# axiom_beta_interface_dummy_v0_9_c4a82e42.net
KiCad netlist of a schematic drawn in EAGLE
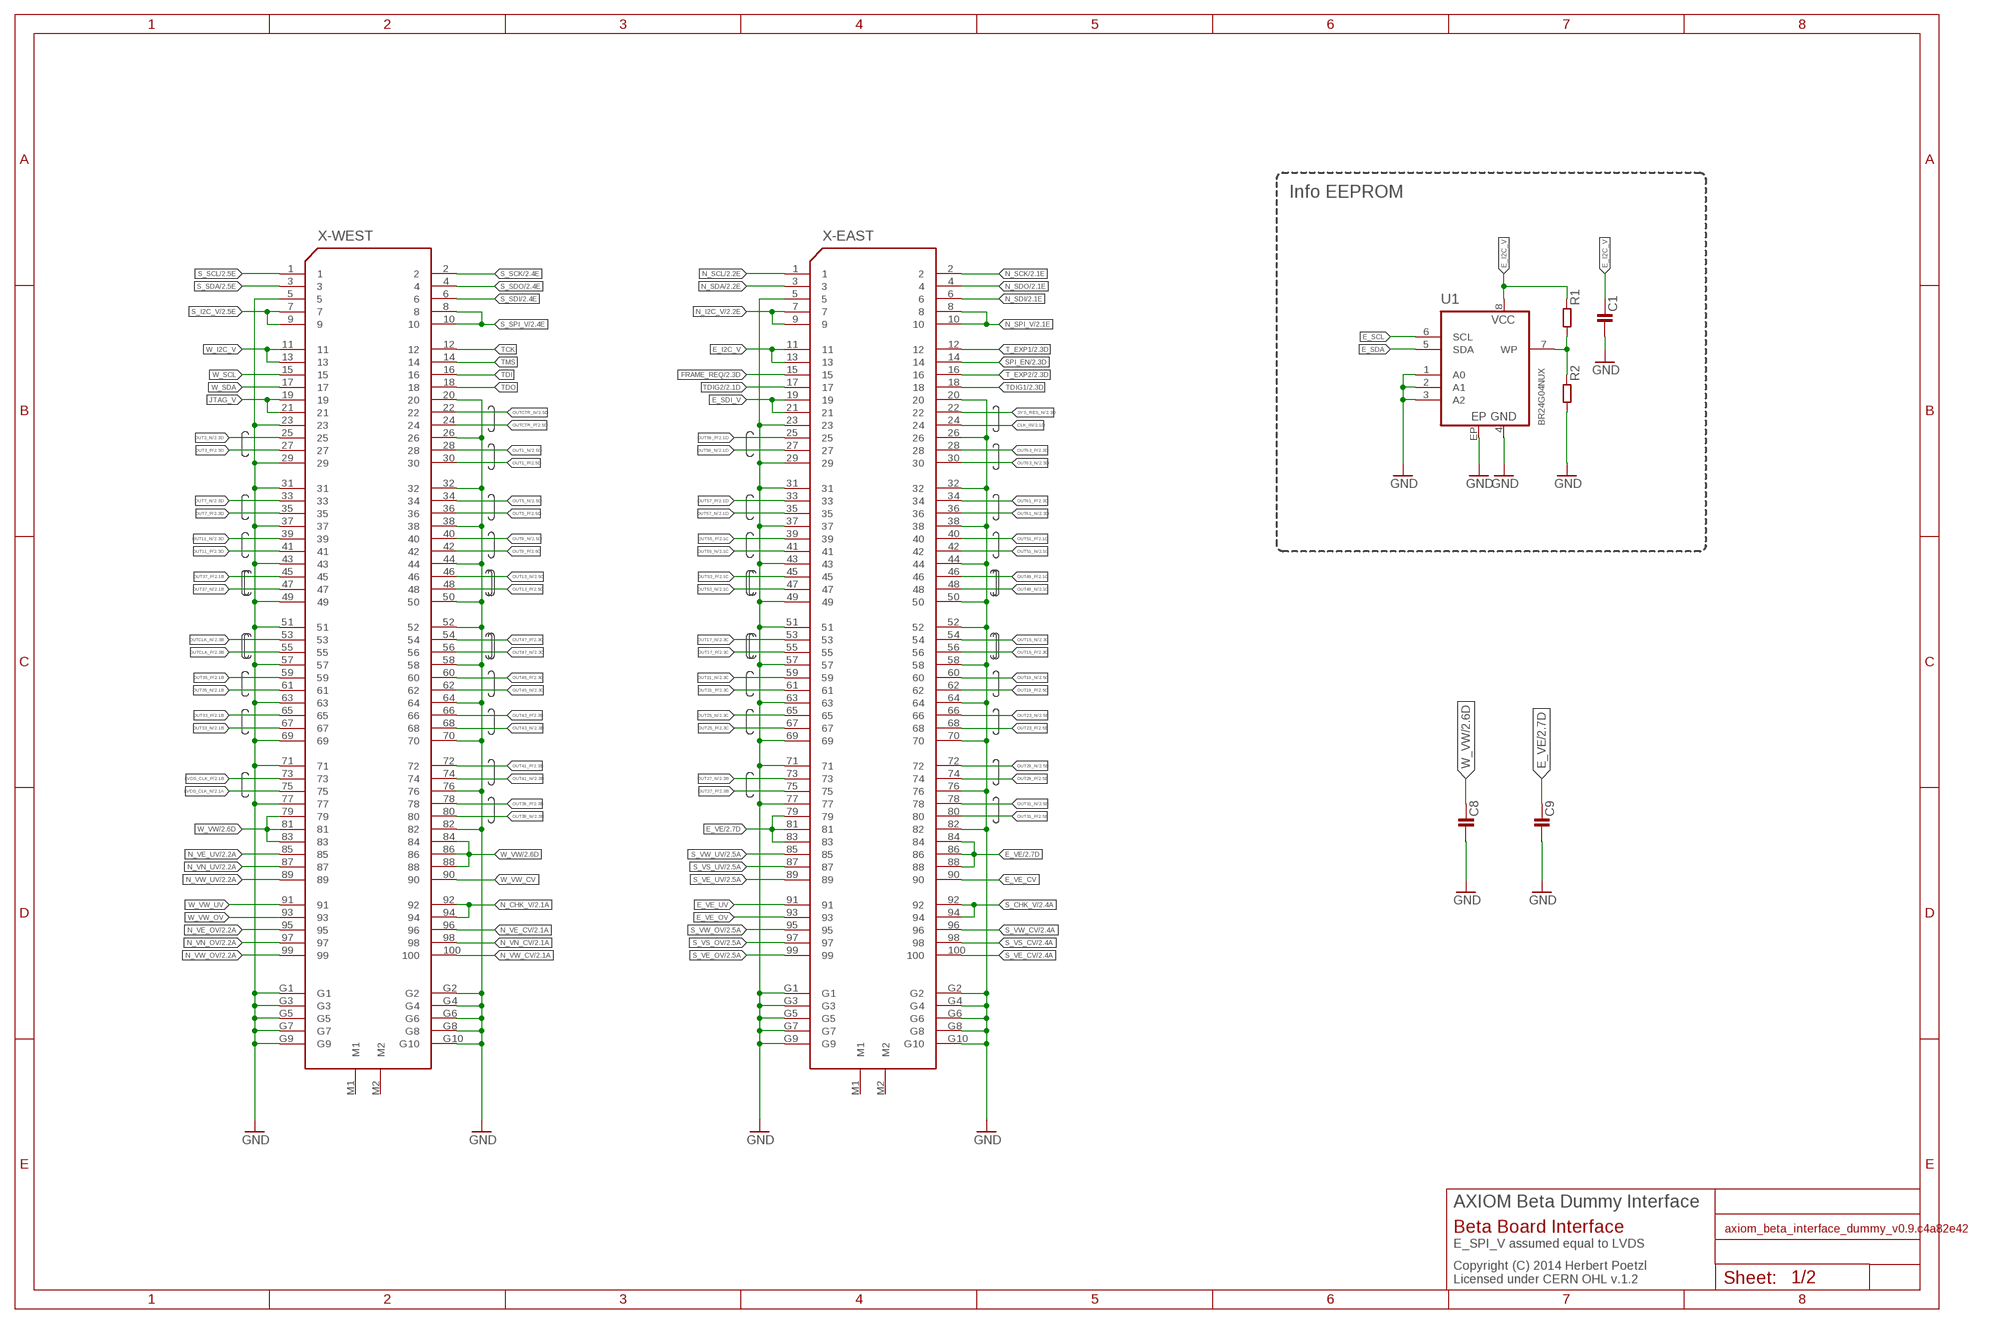
[diagram p0: schematic, sheet 1]
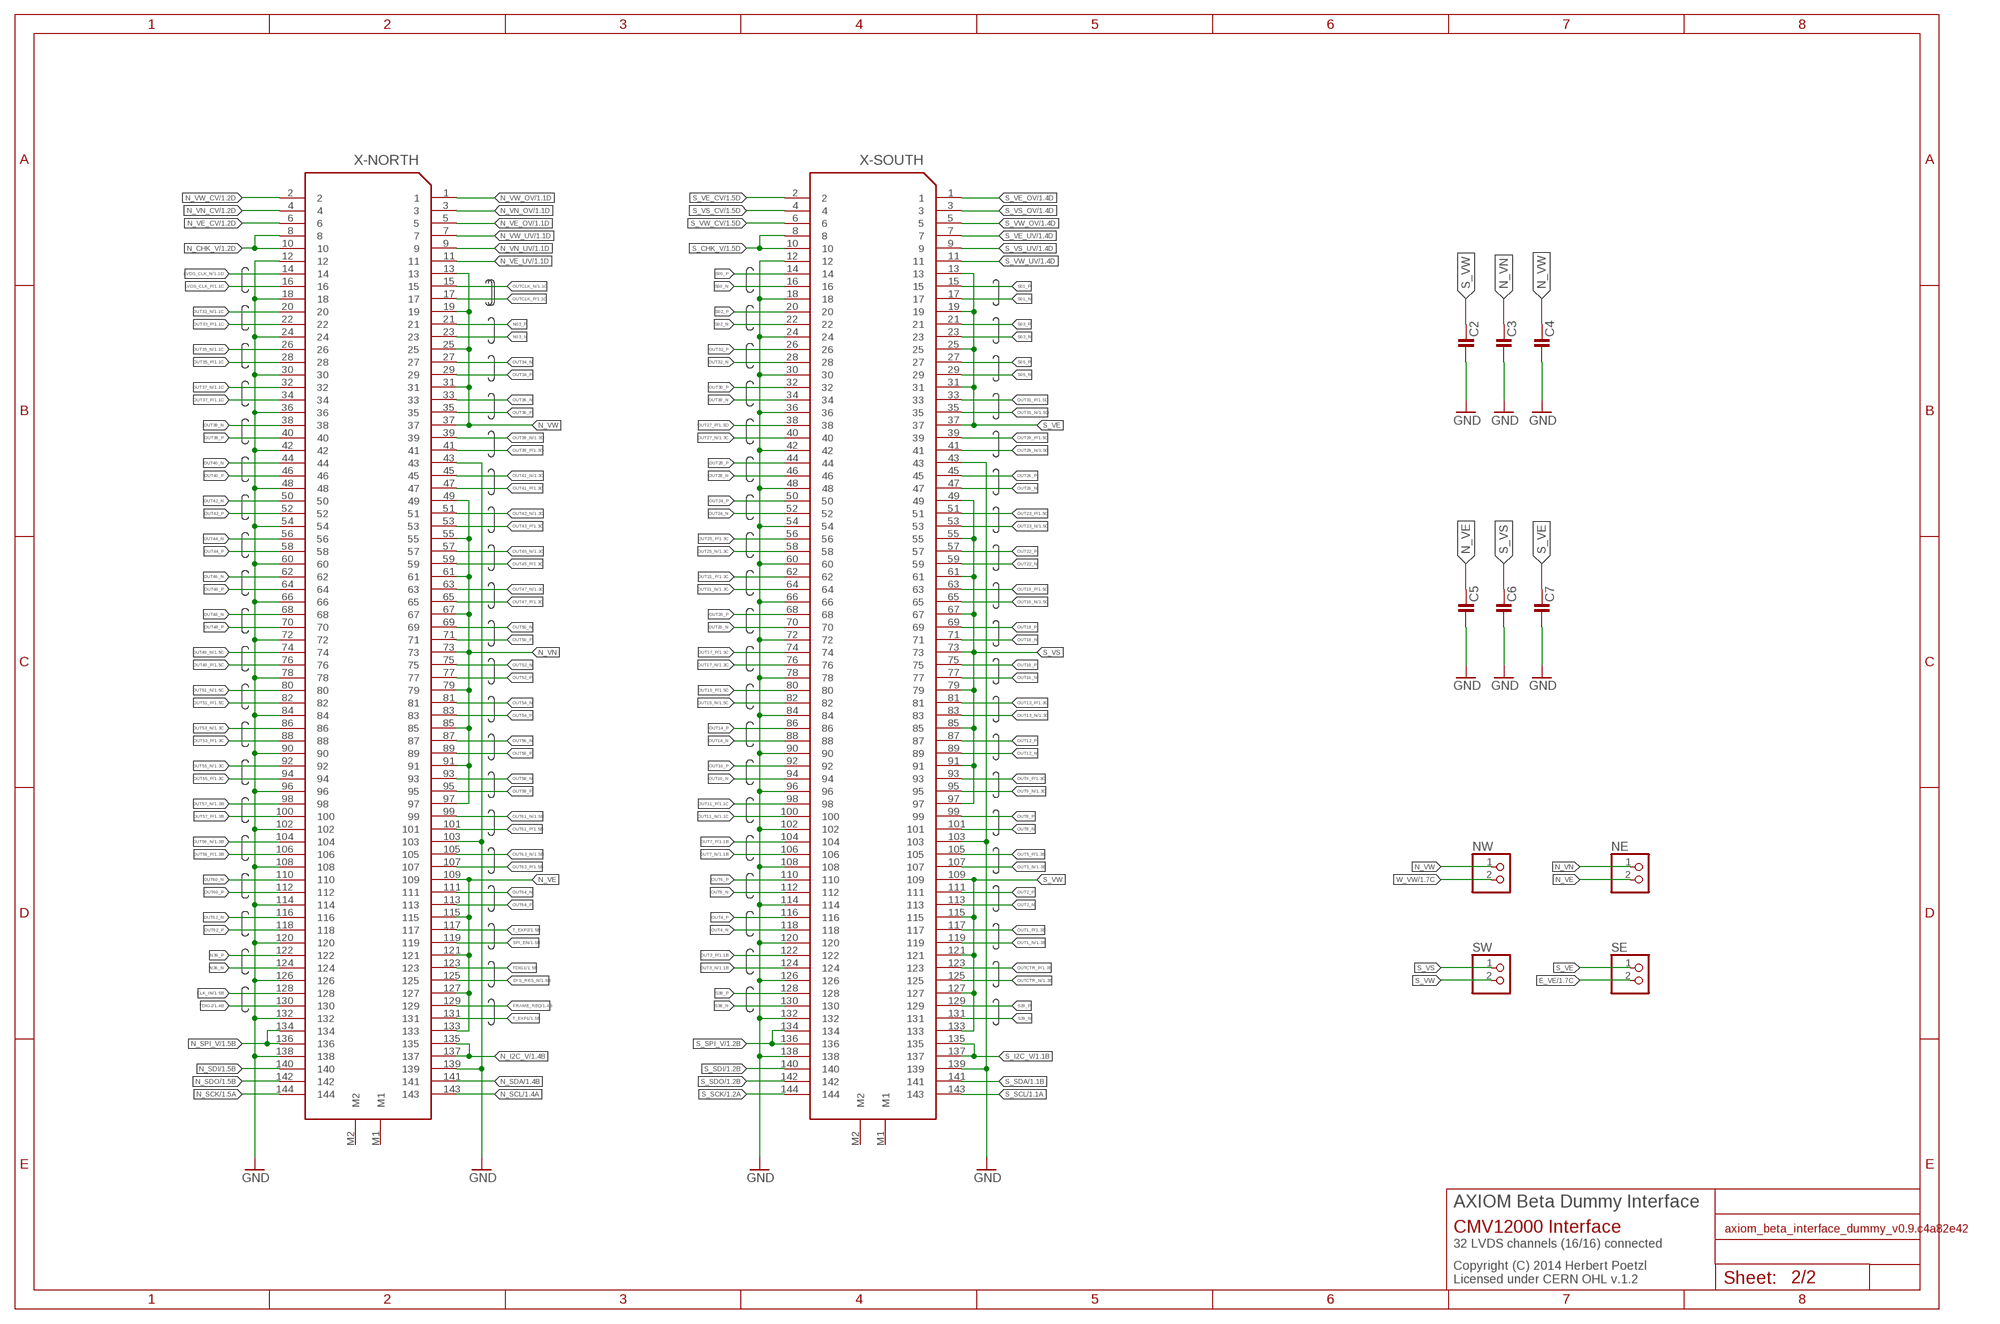
[diagram p1: schematic, sheet 2]

(export (version "E")
  (design (tool "Eeschema 10.0.6"))
  (components
    (comp (ref "C1")
      (value "C0402-B")
      (footprint "eagle-import:0402-B")
      (libsource (lib "eagle-import") (part "C0402-B"))
    )
    (comp (ref "C8")
      (value "C0805-B")
      (footprint "eagle-import:0805-B")
      (libsource (lib "eagle-import") (part "C0805-B"))
    )
    (comp (ref "C9")
      (value "C0805-B")
      (footprint "eagle-import:0805-B")
      (libsource (lib "eagle-import") (part "C0805-B"))
    )
    (comp (ref "R1")
      (value "R0402-B")
      (footprint "eagle-import:0402-B")
      (libsource (lib "eagle-import") (part "R0402-B"))
    )
    (comp (ref "R2")
      (value "R0402-B")
      (footprint "eagle-import:0402-B")
      (libsource (lib "eagle-import") (part "R0402-B"))
    )
    (comp (ref "U1")
      (value "BR24G04NUX")
      (footprint "eagle-import:DFN200X300X100-9N")
      (libsource (lib "eagle-import") (part "BR24G04NUX"))
    )
    (comp (ref "X-EAST")
      (value "FX10-100/10P")
      (footprint "eagle-import:FX10A-100P_10")
      (libsource (lib "eagle-import") (part "FX10-100/10P"))
    )
    (comp (ref "X-WEST")
      (value "FX10-100/10P")
      (footprint "eagle-import:FX10A-100P_10")
      (libsource (lib "eagle-import") (part "FX10-100/10P"))
    )
    (comp (ref "C2")
      (value "C0805-B")
      (footprint "eagle-import:0805-B")
      (libsource (lib "eagle-import") (part "C0805-B"))
    )
    (comp (ref "C3")
      (value "C0805-B")
      (footprint "eagle-import:0805-B")
      (libsource (lib "eagle-import") (part "C0805-B"))
    )
    (comp (ref "C4")
      (value "C0805-B")
      (footprint "eagle-import:0805-B")
      (libsource (lib "eagle-import") (part "C0805-B"))
    )
    (comp (ref "C5")
      (value "C0805-B")
      (footprint "eagle-import:0805-B")
      (libsource (lib "eagle-import") (part "C0805-B"))
    )
    (comp (ref "C6")
      (value "C0805-B")
      (footprint "eagle-import:0805-B")
      (libsource (lib "eagle-import") (part "C0805-B"))
    )
    (comp (ref "C7")
      (value "C0805-B")
      (footprint "eagle-import:0805-B")
      (libsource (lib "eagle-import") (part "C0805-B"))
    )
    (comp (ref "NE")
      (value "PINHD-1X02_2.54")
      (footprint "eagle-import:1X02")
      (libsource (lib "eagle-import") (part "PINHD-1X02_2.54"))
    )
    (comp (ref "NW")
      (value "PINHD-1X02_2.54")
      (footprint "eagle-import:1X02")
      (libsource (lib "eagle-import") (part "PINHD-1X02_2.54"))
    )
    (comp (ref "SE")
      (value "PINHD-1X02_2.54")
      (footprint "eagle-import:1X02")
      (libsource (lib "eagle-import") (part "PINHD-1X02_2.54"))
    )
    (comp (ref "SW")
      (value "PINHD-1X02_2.54")
      (footprint "eagle-import:1X02")
      (libsource (lib "eagle-import") (part "PINHD-1X02_2.54"))
    )
    (comp (ref "X-NORTH")
      (value "FX10-144S")
      (footprint "eagle-import:FX10A-144S")
      (libsource (lib "eagle-import") (part "FX10-144S"))
    )
    (comp (ref "X-SOUTH")
      (value "FX10-144S")
      (footprint "eagle-import:FX10A-144S")
      (libsource (lib "eagle-import") (part "FX10-144S"))
    )
  )
  (nets
    (net (code "1") (name "CLK_IN") (class "Default")
      (node (ref "X-EAST") (pin "24") (pinfunction "24_24") (pintype "bidirectional"))
      (node (ref "X-NORTH") (pin "128") (pinfunction "128_128") (pintype "bidirectional"))
    )
    (net (code "2") (name "E_I2C_V") (class "Default")
      (node (ref "C1") (pin "1") (pinfunction "1_1") (pintype "passive"))
      (node (ref "R1") (pin "1") (pinfunction "1_1") (pintype "passive"))
      (node (ref "U1") (pin "8") (pinfunction "VCC_8") (pintype "power_in"))
      (node (ref "X-EAST") (pin "11") (pinfunction "11_11") (pintype "bidirectional"))
      (node (ref "X-EAST") (pin "13") (pinfunction "13_13") (pintype "bidirectional"))
    )
    (net (code "3") (name "E_SCL") (class "Default")
      (node (ref "U1") (pin "6") (pinfunction "SCL_6") (pintype "input"))
    )
    (net (code "4") (name "E_SDA") (class "Default")
      (node (ref "U1") (pin "5") (pinfunction "SDA_5") (pintype "bidirectional"))
    )
    (net (code "5") (name "E_SDI_V") (class "Default")
      (node (ref "X-EAST") (pin "19") (pinfunction "19_19") (pintype "bidirectional"))
      (node (ref "X-EAST") (pin "21") (pinfunction "21_21") (pintype "bidirectional"))
    )
    (net (code "6") (name "E_VE") (class "Default")
      (node (ref "C9") (pin "1") (pinfunction "1_1") (pintype "passive"))
      (node (ref "SE") (pin "2") (pinfunction "2_2") (pintype "passive"))
      (node (ref "X-EAST") (pin "79") (pinfunction "79_79") (pintype "bidirectional"))
      (node (ref "X-EAST") (pin "81") (pinfunction "81_81") (pintype "bidirectional"))
      (node (ref "X-EAST") (pin "83") (pinfunction "83_83") (pintype "bidirectional"))
      (node (ref "X-EAST") (pin "84") (pinfunction "84_84") (pintype "bidirectional"))
      (node (ref "X-EAST") (pin "86") (pinfunction "86_86") (pintype "bidirectional"))
      (node (ref "X-EAST") (pin "88") (pinfunction "88_88") (pintype "bidirectional"))
    )
    (net (code "7") (name "E_VE_CV") (class "Default")
      (node (ref "X-EAST") (pin "90") (pinfunction "90_90") (pintype "bidirectional"))
    )
    (net (code "8") (name "E_VE_OV") (class "Default")
      (node (ref "X-EAST") (pin "93") (pinfunction "93_93") (pintype "bidirectional"))
    )
    (net (code "9") (name "E_VE_UV") (class "Default")
      (node (ref "X-EAST") (pin "91") (pinfunction "91_91") (pintype "bidirectional"))
    )
    (net (code "10") (name "FRAME_REQ") (class "Default")
      (node (ref "X-EAST") (pin "15") (pinfunction "15_15") (pintype "bidirectional"))
      (node (ref "X-NORTH") (pin "129") (pinfunction "129_129") (pintype "bidirectional"))
    )
    (net (code "11") (name "GND") (class "Default")
      (node (ref "C1") (pin "2") (pinfunction "2_2") (pintype "passive"))
      (node (ref "C2") (pin "2") (pinfunction "2_2") (pintype "passive"))
      (node (ref "C3") (pin "2") (pinfunction "2_2") (pintype "passive"))
      (node (ref "C4") (pin "2") (pinfunction "2_2") (pintype "passive"))
      (node (ref "C5") (pin "2") (pinfunction "2_2") (pintype "passive"))
      (node (ref "C6") (pin "2") (pinfunction "2_2") (pintype "passive"))
      (node (ref "C7") (pin "2") (pinfunction "2_2") (pintype "passive"))
      (node (ref "C8") (pin "2") (pinfunction "2_2") (pintype "passive"))
      (node (ref "C9") (pin "2") (pinfunction "2_2") (pintype "passive"))
      (node (ref "R2") (pin "2") (pinfunction "2_2") (pintype "passive"))
      (node (ref "U1") (pin "1") (pinfunction "A0_1") (pintype "input"))
      (node (ref "U1") (pin "2") (pinfunction "A1_2") (pintype "input"))
      (node (ref "U1") (pin "3") (pinfunction "A2_3") (pintype "input"))
      (node (ref "U1") (pin "4") (pinfunction "GND_4") (pintype "passive"))
      (node (ref "U1") (pin "EP") (pinfunction "EP_EP") (pintype "passive"))
      (node (ref "X-EAST") (pin "20") (pinfunction "20_20") (pintype "bidirectional"))
      (node (ref "X-EAST") (pin "23") (pinfunction "23_23") (pintype "bidirectional"))
      (node (ref "X-EAST") (pin "26") (pinfunction "26_26") (pintype "bidirectional"))
      (node (ref "X-EAST") (pin "29") (pinfunction "29_29") (pintype "bidirectional"))
      (node (ref "X-EAST") (pin "31") (pinfunction "31_31") (pintype "bidirectional"))
      (node (ref "X-EAST") (pin "32") (pinfunction "32_32") (pintype "bidirectional"))
      (node (ref "X-EAST") (pin "37") (pinfunction "37_37") (pintype "bidirectional"))
      (node (ref "X-EAST") (pin "38") (pinfunction "38_38") (pintype "bidirectional"))
      (node (ref "X-EAST") (pin "43") (pinfunction "43_43") (pintype "bidirectional"))
      (node (ref "X-EAST") (pin "44") (pinfunction "44_44") (pintype "bidirectional"))
      (node (ref "X-EAST") (pin "49") (pinfunction "49_49") (pintype "bidirectional"))
      (node (ref "X-EAST") (pin "5") (pinfunction "5_5") (pintype "bidirectional"))
      (node (ref "X-EAST") (pin "50") (pinfunction "50_50") (pintype "bidirectional"))
      (node (ref "X-EAST") (pin "51") (pinfunction "51_51") (pintype "bidirectional"))
      (node (ref "X-EAST") (pin "52") (pinfunction "52_52") (pintype "bidirectional"))
      (node (ref "X-EAST") (pin "57") (pinfunction "57_57") (pintype "bidirectional"))
      (node (ref "X-EAST") (pin "58") (pinfunction "58_58") (pintype "bidirectional"))
      (node (ref "X-EAST") (pin "63") (pinfunction "63_63") (pintype "bidirectional"))
      (node (ref "X-EAST") (pin "64") (pinfunction "64_64") (pintype "bidirectional"))
      (node (ref "X-EAST") (pin "69") (pinfunction "69_69") (pintype "bidirectional"))
      (node (ref "X-EAST") (pin "70") (pinfunction "70_70") (pintype "bidirectional"))
      (node (ref "X-EAST") (pin "71") (pinfunction "71_71") (pintype "bidirectional"))
      (node (ref "X-EAST") (pin "76") (pinfunction "76_76") (pintype "bidirectional"))
      (node (ref "X-EAST") (pin "77") (pinfunction "77_77") (pintype "bidirectional"))
      (node (ref "X-EAST") (pin "82") (pinfunction "82_82") (pintype "bidirectional"))
      (node (ref "X-EAST") (pin "G1") (pinfunction "G1_G1") (pintype "bidirectional"))
      (node (ref "X-EAST") (pin "G10") (pinfunction "G10_G10") (pintype "bidirectional"))
      (node (ref "X-EAST") (pin "G2") (pinfunction "G2_G2") (pintype "bidirectional"))
      (node (ref "X-EAST") (pin "G3") (pinfunction "G3_G3") (pintype "bidirectional"))
      (node (ref "X-EAST") (pin "G4") (pinfunction "G4_G4") (pintype "bidirectional"))
      (node (ref "X-EAST") (pin "G5") (pinfunction "G5_G5") (pintype "bidirectional"))
      (node (ref "X-EAST") (pin "G6") (pinfunction "G6_G6") (pintype "bidirectional"))
      (node (ref "X-EAST") (pin "G7") (pinfunction "G7_G7") (pintype "bidirectional"))
      (node (ref "X-EAST") (pin "G8") (pinfunction "G8_G8") (pintype "bidirectional"))
      (node (ref "X-EAST") (pin "G9") (pinfunction "G9_G9") (pintype "bidirectional"))
      (node (ref "X-NORTH") (pin "102") (pinfunction "102_102") (pintype "bidirectional"))
      (node (ref "X-NORTH") (pin "103") (pinfunction "103_103") (pintype "bidirectional"))
      (node (ref "X-NORTH") (pin "108") (pinfunction "108_108") (pintype "bidirectional"))
      (node (ref "X-NORTH") (pin "114") (pinfunction "114_114") (pintype "bidirectional"))
      (node (ref "X-NORTH") (pin "12") (pinfunction "12_12") (pintype "bidirectional"))
      (node (ref "X-NORTH") (pin "120") (pinfunction "120_120") (pintype "bidirectional"))
      (node (ref "X-NORTH") (pin "126") (pinfunction "126_126") (pintype "bidirectional"))
      (node (ref "X-NORTH") (pin "132") (pinfunction "132_132") (pintype "bidirectional"))
      (node (ref "X-NORTH") (pin "138") (pinfunction "138_138") (pintype "bidirectional"))
      (node (ref "X-NORTH") (pin "139") (pinfunction "139_139") (pintype "bidirectional"))
      (node (ref "X-NORTH") (pin "18") (pinfunction "18_18") (pintype "bidirectional"))
      (node (ref "X-NORTH") (pin "24") (pinfunction "24_24") (pintype "bidirectional"))
      (node (ref "X-NORTH") (pin "30") (pinfunction "30_30") (pintype "bidirectional"))
      (node (ref "X-NORTH") (pin "36") (pinfunction "36_36") (pintype "bidirectional"))
      (node (ref "X-NORTH") (pin "42") (pinfunction "42_42") (pintype "bidirectional"))
      (node (ref "X-NORTH") (pin "43") (pinfunction "43_43") (pintype "bidirectional"))
      (node (ref "X-NORTH") (pin "48") (pinfunction "48_48") (pintype "bidirectional"))
      (node (ref "X-NORTH") (pin "54") (pinfunction "54_54") (pintype "bidirectional"))
      (node (ref "X-NORTH") (pin "60") (pinfunction "60_60") (pintype "bidirectional"))
      (node (ref "X-NORTH") (pin "66") (pinfunction "66_66") (pintype "bidirectional"))
      (node (ref "X-NORTH") (pin "72") (pinfunction "72_72") (pintype "bidirectional"))
      (node (ref "X-NORTH") (pin "78") (pinfunction "78_78") (pintype "bidirectional"))
      (node (ref "X-NORTH") (pin "84") (pinfunction "84_84") (pintype "bidirectional"))
      (node (ref "X-NORTH") (pin "90") (pinfunction "90_90") (pintype "bidirectional"))
      (node (ref "X-NORTH") (pin "96") (pinfunction "96_96") (pintype "bidirectional"))
      (node (ref "X-SOUTH") (pin "102") (pinfunction "102_102") (pintype "bidirectional"))
      (node (ref "X-SOUTH") (pin "103") (pinfunction "103_103") (pintype "bidirectional"))
      (node (ref "X-SOUTH") (pin "108") (pinfunction "108_108") (pintype "bidirectional"))
      (node (ref "X-SOUTH") (pin "114") (pinfunction "114_114") (pintype "bidirectional"))
      (node (ref "X-SOUTH") (pin "12") (pinfunction "12_12") (pintype "bidirectional"))
      (node (ref "X-SOUTH") (pin "120") (pinfunction "120_120") (pintype "bidirectional"))
      (node (ref "X-SOUTH") (pin "126") (pinfunction "126_126") (pintype "bidirectional"))
      (node (ref "X-SOUTH") (pin "132") (pinfunction "132_132") (pintype "bidirectional"))
      (node (ref "X-SOUTH") (pin "138") (pinfunction "138_138") (pintype "bidirectional"))
      (node (ref "X-SOUTH") (pin "139") (pinfunction "139_139") (pintype "bidirectional"))
      (node (ref "X-SOUTH") (pin "18") (pinfunction "18_18") (pintype "bidirectional"))
      (node (ref "X-SOUTH") (pin "24") (pinfunction "24_24") (pintype "bidirectional"))
      (node (ref "X-SOUTH") (pin "30") (pinfunction "30_30") (pintype "bidirectional"))
      (node (ref "X-SOUTH") (pin "36") (pinfunction "36_36") (pintype "bidirectional"))
      (node (ref "X-SOUTH") (pin "42") (pinfunction "42_42") (pintype "bidirectional"))
      (node (ref "X-SOUTH") (pin "43") (pinfunction "43_43") (pintype "bidirectional"))
      (node (ref "X-SOUTH") (pin "48") (pinfunction "48_48") (pintype "bidirectional"))
      (node (ref "X-SOUTH") (pin "54") (pinfunction "54_54") (pintype "bidirectional"))
      (node (ref "X-SOUTH") (pin "60") (pinfunction "60_60") (pintype "bidirectional"))
      (node (ref "X-SOUTH") (pin "66") (pinfunction "66_66") (pintype "bidirectional"))
      (node (ref "X-SOUTH") (pin "72") (pinfunction "72_72") (pintype "bidirectional"))
      (node (ref "X-SOUTH") (pin "78") (pinfunction "78_78") (pintype "bidirectional"))
      (node (ref "X-SOUTH") (pin "84") (pinfunction "84_84") (pintype "bidirectional"))
      (node (ref "X-SOUTH") (pin "90") (pinfunction "90_90") (pintype "bidirectional"))
      (node (ref "X-SOUTH") (pin "96") (pinfunction "96_96") (pintype "bidirectional"))
      (node (ref "X-WEST") (pin "20") (pinfunction "20_20") (pintype "bidirectional"))
      (node (ref "X-WEST") (pin "23") (pinfunction "23_23") (pintype "bidirectional"))
      (node (ref "X-WEST") (pin "26") (pinfunction "26_26") (pintype "bidirectional"))
      (node (ref "X-WEST") (pin "29") (pinfunction "29_29") (pintype "bidirectional"))
      (node (ref "X-WEST") (pin "31") (pinfunction "31_31") (pintype "bidirectional"))
      (node (ref "X-WEST") (pin "32") (pinfunction "32_32") (pintype "bidirectional"))
      (node (ref "X-WEST") (pin "37") (pinfunction "37_37") (pintype "bidirectional"))
      (node (ref "X-WEST") (pin "38") (pinfunction "38_38") (pintype "bidirectional"))
      (node (ref "X-WEST") (pin "43") (pinfunction "43_43") (pintype "bidirectional"))
      (node (ref "X-WEST") (pin "44") (pinfunction "44_44") (pintype "bidirectional"))
      (node (ref "X-WEST") (pin "49") (pinfunction "49_49") (pintype "bidirectional"))
      (node (ref "X-WEST") (pin "5") (pinfunction "5_5") (pintype "bidirectional"))
      (node (ref "X-WEST") (pin "50") (pinfunction "50_50") (pintype "bidirectional"))
      (node (ref "X-WEST") (pin "51") (pinfunction "51_51") (pintype "bidirectional"))
      (node (ref "X-WEST") (pin "52") (pinfunction "52_52") (pintype "bidirectional"))
      (node (ref "X-WEST") (pin "57") (pinfunction "57_57") (pintype "bidirectional"))
      (node (ref "X-WEST") (pin "58") (pinfunction "58_58") (pintype "bidirectional"))
      (node (ref "X-WEST") (pin "63") (pinfunction "63_63") (pintype "bidirectional"))
      (node (ref "X-WEST") (pin "64") (pinfunction "64_64") (pintype "bidirectional"))
      (node (ref "X-WEST") (pin "69") (pinfunction "69_69") (pintype "bidirectional"))
      (node (ref "X-WEST") (pin "70") (pinfunction "70_70") (pintype "bidirectional"))
      (node (ref "X-WEST") (pin "71") (pinfunction "71_71") (pintype "bidirectional"))
      (node (ref "X-WEST") (pin "76") (pinfunction "76_76") (pintype "bidirectional"))
      (node (ref "X-WEST") (pin "77") (pinfunction "77_77") (pintype "bidirectional"))
      (node (ref "X-WEST") (pin "82") (pinfunction "82_82") (pintype "bidirectional"))
      (node (ref "X-WEST") (pin "G1") (pinfunction "G1_G1") (pintype "bidirectional"))
      (node (ref "X-WEST") (pin "G10") (pinfunction "G10_G10") (pintype "bidirectional"))
      (node (ref "X-WEST") (pin "G2") (pinfunction "G2_G2") (pintype "bidirectional"))
      (node (ref "X-WEST") (pin "G3") (pinfunction "G3_G3") (pintype "bidirectional"))
      (node (ref "X-WEST") (pin "G4") (pinfunction "G4_G4") (pintype "bidirectional"))
      (node (ref "X-WEST") (pin "G5") (pinfunction "G5_G5") (pintype "bidirectional"))
      (node (ref "X-WEST") (pin "G6") (pinfunction "G6_G6") (pintype "bidirectional"))
      (node (ref "X-WEST") (pin "G7") (pinfunction "G7_G7") (pintype "bidirectional"))
      (node (ref "X-WEST") (pin "G8") (pinfunction "G8_G8") (pintype "bidirectional"))
      (node (ref "X-WEST") (pin "G9") (pinfunction "G9_G9") (pintype "bidirectional"))
    )
    (net (code "12") (name "JTAG_V") (class "Default")
      (node (ref "X-WEST") (pin "19") (pinfunction "19_19") (pintype "bidirectional"))
      (node (ref "X-WEST") (pin "21") (pinfunction "21_21") (pintype "bidirectional"))
    )
    (net (code "13") (name "LVDS_CLK_N") (class "Default")
      (node (ref "X-NORTH") (pin "14") (pinfunction "14_14") (pintype "bidirectional"))
      (node (ref "X-WEST") (pin "75") (pinfunction "75_75") (pintype "bidirectional"))
    )
    (net (code "14") (name "LVDS_CLK_P") (class "Default")
      (node (ref "X-NORTH") (pin "16") (pinfunction "16_16") (pintype "bidirectional"))
      (node (ref "X-WEST") (pin "73") (pinfunction "73_73") (pintype "bidirectional"))
    )
    (net (code "15") (name "N03_N") (class "Default")
      (node (ref "X-NORTH") (pin "23") (pinfunction "23_23") (pintype "bidirectional"))
    )
    (net (code "16") (name "N03_P") (class "Default")
      (node (ref "X-NORTH") (pin "21") (pinfunction "21_21") (pintype "bidirectional"))
    )
    (net (code "17") (name "N36_N") (class "Default")
      (node (ref "X-NORTH") (pin "124") (pinfunction "124_124") (pintype "bidirectional"))
    )
    (net (code "18") (name "N36_P") (class "Default")
      (node (ref "X-NORTH") (pin "122") (pinfunction "122_122") (pintype "bidirectional"))
    )
    (net (code "19") (name "N_CHK_V") (class "Default")
      (node (ref "X-NORTH") (pin "10") (pinfunction "10_10") (pintype "bidirectional"))
      (node (ref "X-NORTH") (pin "8") (pinfunction "8_8") (pintype "bidirectional"))
      (node (ref "X-WEST") (pin "92") (pinfunction "92_92") (pintype "bidirectional"))
      (node (ref "X-WEST") (pin "94") (pinfunction "94_94") (pintype "bidirectional"))
    )
    (net (code "20") (name "N_I2C_V") (class "Default")
      (node (ref "X-EAST") (pin "7") (pinfunction "7_7") (pintype "bidirectional"))
      (node (ref "X-EAST") (pin "9") (pinfunction "9_9") (pintype "bidirectional"))
      (node (ref "X-NORTH") (pin "135") (pinfunction "135_135") (pintype "bidirectional"))
      (node (ref "X-NORTH") (pin "137") (pinfunction "137_137") (pintype "bidirectional"))
    )
    (net (code "21") (name "N_SCK") (class "Default")
      (node (ref "X-EAST") (pin "2") (pinfunction "2_2") (pintype "bidirectional"))
      (node (ref "X-NORTH") (pin "144") (pinfunction "144_144") (pintype "bidirectional"))
    )
    (net (code "22") (name "N_SCL") (class "Default")
      (node (ref "X-EAST") (pin "1") (pinfunction "1_1") (pintype "bidirectional"))
      (node (ref "X-NORTH") (pin "143") (pinfunction "143_143") (pintype "bidirectional"))
    )
    (net (code "23") (name "N_SDA") (class "Default")
      (node (ref "X-EAST") (pin "3") (pinfunction "3_3") (pintype "bidirectional"))
      (node (ref "X-NORTH") (pin "141") (pinfunction "141_141") (pintype "bidirectional"))
    )
    (net (code "24") (name "N_SDI") (class "Default")
      (node (ref "X-EAST") (pin "6") (pinfunction "6_6") (pintype "bidirectional"))
      (node (ref "X-NORTH") (pin "140") (pinfunction "140_140") (pintype "bidirectional"))
    )
    (net (code "25") (name "N_SDO") (class "Default")
      (node (ref "X-EAST") (pin "4") (pinfunction "4_4") (pintype "bidirectional"))
      (node (ref "X-NORTH") (pin "142") (pinfunction "142_142") (pintype "bidirectional"))
    )
    (net (code "26") (name "N_SPI_V") (class "Default")
      (node (ref "X-EAST") (pin "10") (pinfunction "10_10") (pintype "bidirectional"))
      (node (ref "X-EAST") (pin "8") (pinfunction "8_8") (pintype "bidirectional"))
      (node (ref "X-NORTH") (pin "134") (pinfunction "134_134") (pintype "bidirectional"))
      (node (ref "X-NORTH") (pin "136") (pinfunction "136_136") (pintype "bidirectional"))
    )
    (net (code "27") (name "N_VE") (class "Default")
      (node (ref "C5") (pin "1") (pinfunction "1_1") (pintype "passive"))
      (node (ref "NE") (pin "2") (pinfunction "2_2") (pintype "passive"))
      (node (ref "X-NORTH") (pin "109") (pinfunction "109_109") (pintype "bidirectional"))
      (node (ref "X-NORTH") (pin "115") (pinfunction "115_115") (pintype "bidirectional"))
      (node (ref "X-NORTH") (pin "121") (pinfunction "121_121") (pintype "bidirectional"))
      (node (ref "X-NORTH") (pin "127") (pinfunction "127_127") (pintype "bidirectional"))
      (node (ref "X-NORTH") (pin "133") (pinfunction "133_133") (pintype "bidirectional"))
    )
    (net (code "28") (name "N_VE_CV") (class "Default")
      (node (ref "X-NORTH") (pin "6") (pinfunction "6_6") (pintype "bidirectional"))
      (node (ref "X-WEST") (pin "96") (pinfunction "96_96") (pintype "bidirectional"))
    )
    (net (code "29") (name "N_VE_OV") (class "Default")
      (node (ref "X-NORTH") (pin "5") (pinfunction "5_5") (pintype "bidirectional"))
      (node (ref "X-WEST") (pin "95") (pinfunction "95_95") (pintype "bidirectional"))
    )
    (net (code "30") (name "N_VE_UV") (class "Default")
      (node (ref "X-NORTH") (pin "11") (pinfunction "11_11") (pintype "bidirectional"))
      (node (ref "X-WEST") (pin "85") (pinfunction "85_85") (pintype "bidirectional"))
    )
    (net (code "31") (name "N_VN") (class "Default")
      (node (ref "C3") (pin "1") (pinfunction "1_1") (pintype "passive"))
      (node (ref "NE") (pin "1") (pinfunction "1_1") (pintype "passive"))
      (node (ref "X-NORTH") (pin "49") (pinfunction "49_49") (pintype "bidirectional"))
      (node (ref "X-NORTH") (pin "55") (pinfunction "55_55") (pintype "bidirectional"))
      (node (ref "X-NORTH") (pin "61") (pinfunction "61_61") (pintype "bidirectional"))
      (node (ref "X-NORTH") (pin "67") (pinfunction "67_67") (pintype "bidirectional"))
      (node (ref "X-NORTH") (pin "73") (pinfunction "73_73") (pintype "bidirectional"))
      (node (ref "X-NORTH") (pin "79") (pinfunction "79_79") (pintype "bidirectional"))
      (node (ref "X-NORTH") (pin "85") (pinfunction "85_85") (pintype "bidirectional"))
      (node (ref "X-NORTH") (pin "91") (pinfunction "91_91") (pintype "bidirectional"))
      (node (ref "X-NORTH") (pin "97") (pinfunction "97_97") (pintype "bidirectional"))
    )
    (net (code "32") (name "N_VN_CV") (class "Default")
      (node (ref "X-NORTH") (pin "4") (pinfunction "4_4") (pintype "bidirectional"))
      (node (ref "X-WEST") (pin "98") (pinfunction "98_98") (pintype "bidirectional"))
    )
    (net (code "33") (name "N_VN_OV") (class "Default")
      (node (ref "X-NORTH") (pin "3") (pinfunction "3_3") (pintype "bidirectional"))
      (node (ref "X-WEST") (pin "97") (pinfunction "97_97") (pintype "bidirectional"))
    )
    (net (code "34") (name "N_VN_UV") (class "Default")
      (node (ref "X-NORTH") (pin "9") (pinfunction "9_9") (pintype "bidirectional"))
      (node (ref "X-WEST") (pin "87") (pinfunction "87_87") (pintype "bidirectional"))
    )
    (net (code "35") (name "N_VW") (class "Default")
      (node (ref "C4") (pin "1") (pinfunction "1_1") (pintype "passive"))
      (node (ref "NW") (pin "1") (pinfunction "1_1") (pintype "passive"))
      (node (ref "X-NORTH") (pin "13") (pinfunction "13_13") (pintype "bidirectional"))
      (node (ref "X-NORTH") (pin "19") (pinfunction "19_19") (pintype "bidirectional"))
      (node (ref "X-NORTH") (pin "25") (pinfunction "25_25") (pintype "bidirectional"))
      (node (ref "X-NORTH") (pin "31") (pinfunction "31_31") (pintype "bidirectional"))
      (node (ref "X-NORTH") (pin "37") (pinfunction "37_37") (pintype "bidirectional"))
    )
    (net (code "36") (name "N_VW_CV") (class "Default")
      (node (ref "X-NORTH") (pin "2") (pinfunction "2_2") (pintype "bidirectional"))
      (node (ref "X-WEST") (pin "100") (pinfunction "100_100") (pintype "bidirectional"))
    )
    (net (code "37") (name "N_VW_OV") (class "Default")
      (node (ref "X-NORTH") (pin "1") (pinfunction "1_1") (pintype "bidirectional"))
      (node (ref "X-WEST") (pin "99") (pinfunction "99_99") (pintype "bidirectional"))
    )
    (net (code "38") (name "N_VW_UV") (class "Default")
      (node (ref "X-NORTH") (pin "7") (pinfunction "7_7") (pintype "bidirectional"))
      (node (ref "X-WEST") (pin "89") (pinfunction "89_89") (pintype "bidirectional"))
    )
    (net (code "39") (name "Net-(U1-WP)") (class "Default")
      (node (ref "R1") (pin "2") (pinfunction "2_2") (pintype "passive"))
      (node (ref "R2") (pin "1") (pinfunction "1_1") (pintype "passive"))
      (node (ref "U1") (pin "7") (pinfunction "WP_7") (pintype "input"))
    )
    (net (code "40") (name "OUT1_N") (class "Default")
      (node (ref "X-SOUTH") (pin "119") (pinfunction "119_119") (pintype "bidirectional"))
      (node (ref "X-WEST") (pin "28") (pinfunction "28_28") (pintype "bidirectional"))
    )
    (net (code "41") (name "OUT1_P") (class "Default")
      (node (ref "X-SOUTH") (pin "117") (pinfunction "117_117") (pintype "bidirectional"))
      (node (ref "X-WEST") (pin "30") (pinfunction "30_30") (pintype "bidirectional"))
    )
    (net (code "42") (name "OUT2_N") (class "Default")
      (node (ref "X-SOUTH") (pin "113") (pinfunction "113_113") (pintype "bidirectional"))
    )
    (net (code "43") (name "OUT2_P") (class "Default")
      (node (ref "X-SOUTH") (pin "111") (pinfunction "111_111") (pintype "bidirectional"))
    )
    (net (code "44") (name "OUT3_N") (class "Default")
      (node (ref "X-SOUTH") (pin "124") (pinfunction "124_124") (pintype "bidirectional"))
      (node (ref "X-WEST") (pin "25") (pinfunction "25_25") (pintype "bidirectional"))
    )
    (net (code "45") (name "OUT3_P") (class "Default")
      (node (ref "X-SOUTH") (pin "122") (pinfunction "122_122") (pintype "bidirectional"))
      (node (ref "X-WEST") (pin "27") (pinfunction "27_27") (pintype "bidirectional"))
    )
    (net (code "46") (name "OUT4_N") (class "Default")
      (node (ref "X-SOUTH") (pin "118") (pinfunction "118_118") (pintype "bidirectional"))
    )
    (net (code "47") (name "OUT4_P") (class "Default")
      (node (ref "X-SOUTH") (pin "116") (pinfunction "116_116") (pintype "bidirectional"))
    )
    (net (code "48") (name "OUT5_N") (class "Default")
      (node (ref "X-SOUTH") (pin "107") (pinfunction "107_107") (pintype "bidirectional"))
      (node (ref "X-WEST") (pin "34") (pinfunction "34_34") (pintype "bidirectional"))
    )
    (net (code "49") (name "OUT5_P") (class "Default")
      (node (ref "X-SOUTH") (pin "105") (pinfunction "105_105") (pintype "bidirectional"))
      (node (ref "X-WEST") (pin "36") (pinfunction "36_36") (pintype "bidirectional"))
    )
    (net (code "50") (name "OUT6_N") (class "Default")
      (node (ref "X-SOUTH") (pin "112") (pinfunction "112_112") (pintype "bidirectional"))
    )
    (net (code "51") (name "OUT6_P") (class "Default")
      (node (ref "X-SOUTH") (pin "110") (pinfunction "110_110") (pintype "bidirectional"))
    )
    (net (code "52") (name "OUT7_N") (class "Default")
      (node (ref "X-SOUTH") (pin "106") (pinfunction "106_106") (pintype "bidirectional"))
      (node (ref "X-WEST") (pin "33") (pinfunction "33_33") (pintype "bidirectional"))
    )
    (net (code "53") (name "OUT7_P") (class "Default")
      (node (ref "X-SOUTH") (pin "104") (pinfunction "104_104") (pintype "bidirectional"))
      (node (ref "X-WEST") (pin "35") (pinfunction "35_35") (pintype "bidirectional"))
    )
    (net (code "54") (name "OUT8_N") (class "Default")
      (node (ref "X-SOUTH") (pin "101") (pinfunction "101_101") (pintype "bidirectional"))
    )
    (net (code "55") (name "OUT8_P") (class "Default")
      (node (ref "X-SOUTH") (pin "99") (pinfunction "99_99") (pintype "bidirectional"))
    )
    (net (code "56") (name "OUT9_N") (class "Default")
      (node (ref "X-SOUTH") (pin "95") (pinfunction "95_95") (pintype "bidirectional"))
      (node (ref "X-WEST") (pin "40") (pinfunction "40_40") (pintype "bidirectional"))
    )
    (net (code "57") (name "OUT9_P") (class "Default")
      (node (ref "X-SOUTH") (pin "93") (pinfunction "93_93") (pintype "bidirectional"))
      (node (ref "X-WEST") (pin "42") (pinfunction "42_42") (pintype "bidirectional"))
    )
    (net (code "58") (name "OUT10_N") (class "Default")
      (node (ref "X-SOUTH") (pin "94") (pinfunction "94_94") (pintype "bidirectional"))
    )
    (net (code "59") (name "OUT10_P") (class "Default")
      (node (ref "X-SOUTH") (pin "92") (pinfunction "92_92") (pintype "bidirectional"))
    )
    (net (code "60") (name "OUT11_N") (class "Default")
      (node (ref "X-SOUTH") (pin "100") (pinfunction "100_100") (pintype "bidirectional"))
      (node (ref "X-WEST") (pin "39") (pinfunction "39_39") (pintype "bidirectional"))
    )
    (net (code "61") (name "OUT11_P") (class "Default")
      (node (ref "X-SOUTH") (pin "98") (pinfunction "98_98") (pintype "bidirectional"))
      (node (ref "X-WEST") (pin "41") (pinfunction "41_41") (pintype "bidirectional"))
    )
    (net (code "62") (name "OUT12_N") (class "Default")
      (node (ref "X-SOUTH") (pin "89") (pinfunction "89_89") (pintype "bidirectional"))
    )
    (net (code "63") (name "OUT12_P") (class "Default")
      (node (ref "X-SOUTH") (pin "87") (pinfunction "87_87") (pintype "bidirectional"))
    )
    (net (code "64") (name "OUT13_N") (class "Default")
      (node (ref "X-SOUTH") (pin "83") (pinfunction "83_83") (pintype "bidirectional"))
      (node (ref "X-WEST") (pin "46") (pinfunction "46_46") (pintype "bidirectional"))
    )
    (net (code "65") (name "OUT13_P") (class "Default")
      (node (ref "X-SOUTH") (pin "81") (pinfunction "81_81") (pintype "bidirectional"))
      (node (ref "X-WEST") (pin "48") (pinfunction "48_48") (pintype "bidirectional"))
    )
    (net (code "66") (name "OUT14_N") (class "Default")
      (node (ref "X-SOUTH") (pin "88") (pinfunction "88_88") (pintype "bidirectional"))
    )
    (net (code "67") (name "OUT14_P") (class "Default")
      (node (ref "X-SOUTH") (pin "86") (pinfunction "86_86") (pintype "bidirectional"))
    )
    (net (code "68") (name "OUT15_N") (class "Default")
      (node (ref "X-EAST") (pin "54") (pinfunction "54_54") (pintype "bidirectional"))
      (node (ref "X-SOUTH") (pin "82") (pinfunction "82_82") (pintype "bidirectional"))
    )
    (net (code "69") (name "OUT15_P") (class "Default")
      (node (ref "X-EAST") (pin "56") (pinfunction "56_56") (pintype "bidirectional"))
      (node (ref "X-SOUTH") (pin "80") (pinfunction "80_80") (pintype "bidirectional"))
    )
    (net (code "70") (name "OUT16_N") (class "Default")
      (node (ref "X-SOUTH") (pin "77") (pinfunction "77_77") (pintype "bidirectional"))
    )
    (net (code "71") (name "OUT16_P") (class "Default")
      (node (ref "X-SOUTH") (pin "75") (pinfunction "75_75") (pintype "bidirectional"))
    )
    (net (code "72") (name "OUT17_N") (class "Default")
      (node (ref "X-EAST") (pin "53") (pinfunction "53_53") (pintype "bidirectional"))
      (node (ref "X-SOUTH") (pin "76") (pinfunction "76_76") (pintype "bidirectional"))
    )
    (net (code "73") (name "OUT17_P") (class "Default")
      (node (ref "X-EAST") (pin "55") (pinfunction "55_55") (pintype "bidirectional"))
      (node (ref "X-SOUTH") (pin "74") (pinfunction "74_74") (pintype "bidirectional"))
    )
    (net (code "74") (name "OUT18_N") (class "Default")
      (node (ref "X-SOUTH") (pin "71") (pinfunction "71_71") (pintype "bidirectional"))
    )
    (net (code "75") (name "OUT18_P") (class "Default")
      (node (ref "X-SOUTH") (pin "69") (pinfunction "69_69") (pintype "bidirectional"))
    )
    (net (code "76") (name "OUT19_N") (class "Default")
      (node (ref "X-EAST") (pin "60") (pinfunction "60_60") (pintype "bidirectional"))
      (node (ref "X-SOUTH") (pin "65") (pinfunction "65_65") (pintype "bidirectional"))
    )
    (net (code "77") (name "OUT19_P") (class "Default")
      (node (ref "X-EAST") (pin "62") (pinfunction "62_62") (pintype "bidirectional"))
      (node (ref "X-SOUTH") (pin "63") (pinfunction "63_63") (pintype "bidirectional"))
    )
    (net (code "78") (name "OUT20_N") (class "Default")
      (node (ref "X-SOUTH") (pin "70") (pinfunction "70_70") (pintype "bidirectional"))
    )
    (net (code "79") (name "OUT20_P") (class "Default")
      (node (ref "X-SOUTH") (pin "68") (pinfunction "68_68") (pintype "bidirectional"))
    )
    (net (code "80") (name "OUT21_N") (class "Default")
      (node (ref "X-EAST") (pin "59") (pinfunction "59_59") (pintype "bidirectional"))
      (node (ref "X-SOUTH") (pin "64") (pinfunction "64_64") (pintype "bidirectional"))
    )
    (net (code "81") (name "OUT21_P") (class "Default")
      (node (ref "X-EAST") (pin "61") (pinfunction "61_61") (pintype "bidirectional"))
      (node (ref "X-SOUTH") (pin "62") (pinfunction "62_62") (pintype "bidirectional"))
    )
    (net (code "82") (name "OUT22_N") (class "Default")
      (node (ref "X-SOUTH") (pin "59") (pinfunction "59_59") (pintype "bidirectional"))
    )
    (net (code "83") (name "OUT22_P") (class "Default")
      (node (ref "X-SOUTH") (pin "57") (pinfunction "57_57") (pintype "bidirectional"))
    )
    (net (code "84") (name "OUT23_N") (class "Default")
      (node (ref "X-EAST") (pin "66") (pinfunction "66_66") (pintype "bidirectional"))
      (node (ref "X-SOUTH") (pin "53") (pinfunction "53_53") (pintype "bidirectional"))
    )
    (net (code "85") (name "OUT23_P") (class "Default")
      (node (ref "X-EAST") (pin "68") (pinfunction "68_68") (pintype "bidirectional"))
      (node (ref "X-SOUTH") (pin "51") (pinfunction "51_51") (pintype "bidirectional"))
    )
    (net (code "86") (name "OUT24_N") (class "Default")
      (node (ref "X-SOUTH") (pin "52") (pinfunction "52_52") (pintype "bidirectional"))
    )
    (net (code "87") (name "OUT24_P") (class "Default")
      (node (ref "X-SOUTH") (pin "50") (pinfunction "50_50") (pintype "bidirectional"))
    )
    (net (code "88") (name "OUT25_N") (class "Default")
      (node (ref "X-EAST") (pin "65") (pinfunction "65_65") (pintype "bidirectional"))
      (node (ref "X-SOUTH") (pin "58") (pinfunction "58_58") (pintype "bidirectional"))
    )
    (net (code "89") (name "OUT25_P") (class "Default")
      (node (ref "X-EAST") (pin "67") (pinfunction "67_67") (pintype "bidirectional"))
      (node (ref "X-SOUTH") (pin "56") (pinfunction "56_56") (pintype "bidirectional"))
    )
    (net (code "90") (name "OUT26_N") (class "Default")
      (node (ref "X-SOUTH") (pin "47") (pinfunction "47_47") (pintype "bidirectional"))
    )
    (net (code "91") (name "OUT26_P") (class "Default")
      (node (ref "X-SOUTH") (pin "45") (pinfunction "45_45") (pintype "bidirectional"))
    )
    (net (code "92") (name "OUT27_N") (class "Default")
      (node (ref "X-EAST") (pin "73") (pinfunction "73_73") (pintype "bidirectional"))
      (node (ref "X-SOUTH") (pin "40") (pinfunction "40_40") (pintype "bidirectional"))
    )
    (net (code "93") (name "OUT27_P") (class "Default")
      (node (ref "X-EAST") (pin "75") (pinfunction "75_75") (pintype "bidirectional"))
      (node (ref "X-SOUTH") (pin "38") (pinfunction "38_38") (pintype "bidirectional"))
    )
    (net (code "94") (name "OUT28_N") (class "Default")
      (node (ref "X-SOUTH") (pin "46") (pinfunction "46_46") (pintype "bidirectional"))
    )
    (net (code "95") (name "OUT28_P") (class "Default")
      (node (ref "X-SOUTH") (pin "44") (pinfunction "44_44") (pintype "bidirectional"))
    )
    (net (code "96") (name "OUT29_N") (class "Default")
      (node (ref "X-EAST") (pin "72") (pinfunction "72_72") (pintype "bidirectional"))
      (node (ref "X-SOUTH") (pin "41") (pinfunction "41_41") (pintype "bidirectional"))
    )
    (net (code "97") (name "OUT29_P") (class "Default")
      (node (ref "X-EAST") (pin "74") (pinfunction "74_74") (pintype "bidirectional"))
      (node (ref "X-SOUTH") (pin "39") (pinfunction "39_39") (pintype "bidirectional"))
    )
    (net (code "98") (name "OUT30_N") (class "Default")
      (node (ref "X-SOUTH") (pin "34") (pinfunction "34_34") (pintype "bidirectional"))
    )
    (net (code "99") (name "OUT30_P") (class "Default")
      (node (ref "X-SOUTH") (pin "32") (pinfunction "32_32") (pintype "bidirectional"))
    )
    (net (code "100") (name "OUT31_N") (class "Default")
      (node (ref "X-EAST") (pin "78") (pinfunction "78_78") (pintype "bidirectional"))
      (node (ref "X-SOUTH") (pin "35") (pinfunction "35_35") (pintype "bidirectional"))
    )
    (net (code "101") (name "OUT31_P") (class "Default")
      (node (ref "X-EAST") (pin "80") (pinfunction "80_80") (pintype "bidirectional"))
      (node (ref "X-SOUTH") (pin "33") (pinfunction "33_33") (pintype "bidirectional"))
    )
    (net (code "102") (name "OUT32_N") (class "Default")
      (node (ref "X-SOUTH") (pin "28") (pinfunction "28_28") (pintype "bidirectional"))
    )
    (net (code "103") (name "OUT32_P") (class "Default")
      (node (ref "X-SOUTH") (pin "26") (pinfunction "26_26") (pintype "bidirectional"))
    )
    (net (code "104") (name "OUT33_N") (class "Default")
      (node (ref "X-NORTH") (pin "20") (pinfunction "20_20") (pintype "bidirectional"))
      (node (ref "X-WEST") (pin "67") (pinfunction "67_67") (pintype "bidirectional"))
    )
    (net (code "105") (name "OUT33_P") (class "Default")
      (node (ref "X-NORTH") (pin "22") (pinfunction "22_22") (pintype "bidirectional"))
      (node (ref "X-WEST") (pin "65") (pinfunction "65_65") (pintype "bidirectional"))
    )
    (net (code "106") (name "OUT34_N") (class "Default")
      (node (ref "X-NORTH") (pin "27") (pinfunction "27_27") (pintype "bidirectional"))
    )
    (net (code "107") (name "OUT34_P") (class "Default")
      (node (ref "X-NORTH") (pin "29") (pinfunction "29_29") (pintype "bidirectional"))
    )
    (net (code "108") (name "OUT35_N") (class "Default")
      (node (ref "X-NORTH") (pin "26") (pinfunction "26_26") (pintype "bidirectional"))
      (node (ref "X-WEST") (pin "61") (pinfunction "61_61") (pintype "bidirectional"))
    )
    (net (code "109") (name "OUT35_P") (class "Default")
      (node (ref "X-NORTH") (pin "28") (pinfunction "28_28") (pintype "bidirectional"))
      (node (ref "X-WEST") (pin "59") (pinfunction "59_59") (pintype "bidirectional"))
    )
    (net (code "110") (name "OUT36_N") (class "Default")
      (node (ref "X-NORTH") (pin "33") (pinfunction "33_33") (pintype "bidirectional"))
    )
    (net (code "111") (name "OUT36_P") (class "Default")
      (node (ref "X-NORTH") (pin "35") (pinfunction "35_35") (pintype "bidirectional"))
    )
    (net (code "112") (name "OUT37_N") (class "Default")
      (node (ref "X-NORTH") (pin "32") (pinfunction "32_32") (pintype "bidirectional"))
      (node (ref "X-WEST") (pin "47") (pinfunction "47_47") (pintype "bidirectional"))
    )
    (net (code "113") (name "OUT37_P") (class "Default")
      (node (ref "X-NORTH") (pin "34") (pinfunction "34_34") (pintype "bidirectional"))
      (node (ref "X-WEST") (pin "45") (pinfunction "45_45") (pintype "bidirectional"))
    )
    (net (code "114") (name "OUT38_N") (class "Default")
      (node (ref "X-NORTH") (pin "38") (pinfunction "38_38") (pintype "bidirectional"))
    )
    (net (code "115") (name "OUT38_P") (class "Default")
      (node (ref "X-NORTH") (pin "40") (pinfunction "40_40") (pintype "bidirectional"))
    )
    (net (code "116") (name "OUT39_N") (class "Default")
      (node (ref "X-NORTH") (pin "39") (pinfunction "39_39") (pintype "bidirectional"))
      (node (ref "X-WEST") (pin "80") (pinfunction "80_80") (pintype "bidirectional"))
    )
    (net (code "117") (name "OUT39_P") (class "Default")
      (node (ref "X-NORTH") (pin "41") (pinfunction "41_41") (pintype "bidirectional"))
      (node (ref "X-WEST") (pin "78") (pinfunction "78_78") (pintype "bidirectional"))
    )
    (net (code "118") (name "OUT40_N") (class "Default")
      (node (ref "X-NORTH") (pin "44") (pinfunction "44_44") (pintype "bidirectional"))
    )
    (net (code "119") (name "OUT40_P") (class "Default")
      (node (ref "X-NORTH") (pin "46") (pinfunction "46_46") (pintype "bidirectional"))
    )
    (net (code "120") (name "OUT41_N") (class "Default")
      (node (ref "X-NORTH") (pin "45") (pinfunction "45_45") (pintype "bidirectional"))
      (node (ref "X-WEST") (pin "74") (pinfunction "74_74") (pintype "bidirectional"))
    )
    (net (code "121") (name "OUT41_P") (class "Default")
      (node (ref "X-NORTH") (pin "47") (pinfunction "47_47") (pintype "bidirectional"))
      (node (ref "X-WEST") (pin "72") (pinfunction "72_72") (pintype "bidirectional"))
    )
    (net (code "122") (name "OUT42_N") (class "Default")
      (node (ref "X-NORTH") (pin "50") (pinfunction "50_50") (pintype "bidirectional"))
    )
    (net (code "123") (name "OUT42_P") (class "Default")
      (node (ref "X-NORTH") (pin "52") (pinfunction "52_52") (pintype "bidirectional"))
    )
    (net (code "124") (name "OUT43_N") (class "Default")
      (node (ref "X-NORTH") (pin "51") (pinfunction "51_51") (pintype "bidirectional"))
      (node (ref "X-WEST") (pin "68") (pinfunction "68_68") (pintype "bidirectional"))
    )
    (net (code "125") (name "OUT43_P") (class "Default")
      (node (ref "X-NORTH") (pin "53") (pinfunction "53_53") (pintype "bidirectional"))
      (node (ref "X-WEST") (pin "66") (pinfunction "66_66") (pintype "bidirectional"))
    )
    (net (code "126") (name "OUT44_N") (class "Default")
      (node (ref "X-NORTH") (pin "56") (pinfunction "56_56") (pintype "bidirectional"))
    )
    (net (code "127") (name "OUT44_P") (class "Default")
      (node (ref "X-NORTH") (pin "58") (pinfunction "58_58") (pintype "bidirectional"))
    )
    (net (code "128") (name "OUT45_N") (class "Default")
      (node (ref "X-NORTH") (pin "57") (pinfunction "57_57") (pintype "bidirectional"))
      (node (ref "X-WEST") (pin "62") (pinfunction "62_62") (pintype "bidirectional"))
    )
    (net (code "129") (name "OUT45_P") (class "Default")
      (node (ref "X-NORTH") (pin "59") (pinfunction "59_59") (pintype "bidirectional"))
      (node (ref "X-WEST") (pin "60") (pinfunction "60_60") (pintype "bidirectional"))
    )
    (net (code "130") (name "OUT46_N") (class "Default")
      (node (ref "X-NORTH") (pin "62") (pinfunction "62_62") (pintype "bidirectional"))
    )
    (net (code "131") (name "OUT46_P") (class "Default")
      (node (ref "X-NORTH") (pin "64") (pinfunction "64_64") (pintype "bidirectional"))
    )
    (net (code "132") (name "OUT47_N") (class "Default")
      (node (ref "X-NORTH") (pin "63") (pinfunction "63_63") (pintype "bidirectional"))
      (node (ref "X-WEST") (pin "56") (pinfunction "56_56") (pintype "bidirectional"))
    )
    (net (code "133") (name "OUT47_P") (class "Default")
      (node (ref "X-NORTH") (pin "65") (pinfunction "65_65") (pintype "bidirectional"))
      (node (ref "X-WEST") (pin "54") (pinfunction "54_54") (pintype "bidirectional"))
    )
    (net (code "134") (name "OUT48_N") (class "Default")
      (node (ref "X-NORTH") (pin "68") (pinfunction "68_68") (pintype "bidirectional"))
    )
    (net (code "135") (name "OUT48_P") (class "Default")
      (node (ref "X-NORTH") (pin "70") (pinfunction "70_70") (pintype "bidirectional"))
    )
    (net (code "136") (name "OUT49_N") (class "Default")
      (node (ref "X-EAST") (pin "48") (pinfunction "48_48") (pintype "bidirectional"))
      (node (ref "X-NORTH") (pin "74") (pinfunction "74_74") (pintype "bidirectional"))
    )
    (net (code "137") (name "OUT49_P") (class "Default")
      (node (ref "X-EAST") (pin "46") (pinfunction "46_46") (pintype "bidirectional"))
      (node (ref "X-NORTH") (pin "76") (pinfunction "76_76") (pintype "bidirectional"))
    )
    (net (code "138") (name "OUT50_N") (class "Default")
      (node (ref "X-NORTH") (pin "69") (pinfunction "69_69") (pintype "bidirectional"))
    )
    (net (code "139") (name "OUT50_P") (class "Default")
      (node (ref "X-NORTH") (pin "71") (pinfunction "71_71") (pintype "bidirectional"))
    )
    (net (code "140") (name "OUT51_N") (class "Default")
      (node (ref "X-EAST") (pin "42") (pinfunction "42_42") (pintype "bidirectional"))
      (node (ref "X-NORTH") (pin "80") (pinfunction "80_80") (pintype "bidirectional"))
    )
    (net (code "141") (name "OUT51_P") (class "Default")
      (node (ref "X-EAST") (pin "40") (pinfunction "40_40") (pintype "bidirectional"))
      (node (ref "X-NORTH") (pin "82") (pinfunction "82_82") (pintype "bidirectional"))
    )
    (net (code "142") (name "OUT52_N") (class "Default")
      (node (ref "X-NORTH") (pin "75") (pinfunction "75_75") (pintype "bidirectional"))
    )
    (net (code "143") (name "OUT52_P") (class "Default")
      (node (ref "X-NORTH") (pin "77") (pinfunction "77_77") (pintype "bidirectional"))
    )
    (net (code "144") (name "OUT53_N") (class "Default")
      (node (ref "X-EAST") (pin "47") (pinfunction "47_47") (pintype "bidirectional"))
      (node (ref "X-NORTH") (pin "86") (pinfunction "86_86") (pintype "bidirectional"))
    )
    (net (code "145") (name "OUT53_P") (class "Default")
      (node (ref "X-EAST") (pin "45") (pinfunction "45_45") (pintype "bidirectional"))
      (node (ref "X-NORTH") (pin "88") (pinfunction "88_88") (pintype "bidirectional"))
    )
    (net (code "146") (name "OUT54_N") (class "Default")
      (node (ref "X-NORTH") (pin "81") (pinfunction "81_81") (pintype "bidirectional"))
    )
    (net (code "147") (name "OUT54_P") (class "Default")
      (node (ref "X-NORTH") (pin "83") (pinfunction "83_83") (pintype "bidirectional"))
    )
    (net (code "148") (name "OUT55_N") (class "Default")
      (node (ref "X-EAST") (pin "41") (pinfunction "41_41") (pintype "bidirectional"))
      (node (ref "X-NORTH") (pin "92") (pinfunction "92_92") (pintype "bidirectional"))
    )
    (net (code "149") (name "OUT55_P") (class "Default")
      (node (ref "X-EAST") (pin "39") (pinfunction "39_39") (pintype "bidirectional"))
      (node (ref "X-NORTH") (pin "94") (pinfunction "94_94") (pintype "bidirectional"))
    )
    (net (code "150") (name "OUT56_N") (class "Default")
      (node (ref "X-NORTH") (pin "87") (pinfunction "87_87") (pintype "bidirectional"))
    )
    (net (code "151") (name "OUT56_P") (class "Default")
      (node (ref "X-NORTH") (pin "89") (pinfunction "89_89") (pintype "bidirectional"))
    )
    (net (code "152") (name "OUT57_N") (class "Default")
      (node (ref "X-EAST") (pin "35") (pinfunction "35_35") (pintype "bidirectional"))
      (node (ref "X-NORTH") (pin "98") (pinfunction "98_98") (pintype "bidirectional"))
    )
    (net (code "153") (name "OUT57_P") (class "Default")
      (node (ref "X-EAST") (pin "33") (pinfunction "33_33") (pintype "bidirectional"))
      (node (ref "X-NORTH") (pin "100") (pinfunction "100_100") (pintype "bidirectional"))
    )
    (net (code "154") (name "OUT58_N") (class "Default")
      (node (ref "X-NORTH") (pin "93") (pinfunction "93_93") (pintype "bidirectional"))
    )
    (net (code "155") (name "OUT58_P") (class "Default")
      (node (ref "X-NORTH") (pin "95") (pinfunction "95_95") (pintype "bidirectional"))
    )
    (net (code "156") (name "OUT59_N") (class "Default")
      (node (ref "X-EAST") (pin "27") (pinfunction "27_27") (pintype "bidirectional"))
      (node (ref "X-NORTH") (pin "104") (pinfunction "104_104") (pintype "bidirectional"))
    )
    (net (code "157") (name "OUT59_P") (class "Default")
      (node (ref "X-EAST") (pin "25") (pinfunction "25_25") (pintype "bidirectional"))
      (node (ref "X-NORTH") (pin "106") (pinfunction "106_106") (pintype "bidirectional"))
    )
    (net (code "158") (name "OUT60_N") (class "Default")
      (node (ref "X-NORTH") (pin "110") (pinfunction "110_110") (pintype "bidirectional"))
    )
    (net (code "159") (name "OUT60_P") (class "Default")
      (node (ref "X-NORTH") (pin "112") (pinfunction "112_112") (pintype "bidirectional"))
    )
    (net (code "160") (name "OUT61_N") (class "Default")
      (node (ref "X-EAST") (pin "36") (pinfunction "36_36") (pintype "bidirectional"))
      (node (ref "X-NORTH") (pin "99") (pinfunction "99_99") (pintype "bidirectional"))
    )
    (net (code "161") (name "OUT61_P") (class "Default")
      (node (ref "X-EAST") (pin "34") (pinfunction "34_34") (pintype "bidirectional"))
      (node (ref "X-NORTH") (pin "101") (pinfunction "101_101") (pintype "bidirectional"))
    )
    (net (code "162") (name "OUT62_N") (class "Default")
      (node (ref "X-NORTH") (pin "116") (pinfunction "116_116") (pintype "bidirectional"))
    )
    (net (code "163") (name "OUT62_P") (class "Default")
      (node (ref "X-NORTH") (pin "118") (pinfunction "118_118") (pintype "bidirectional"))
    )
    (net (code "164") (name "OUT63_N") (class "Default")
      (node (ref "X-EAST") (pin "30") (pinfunction "30_30") (pintype "bidirectional"))
      (node (ref "X-NORTH") (pin "105") (pinfunction "105_105") (pintype "bidirectional"))
    )
    (net (code "165") (name "OUT63_P") (class "Default")
      (node (ref "X-EAST") (pin "28") (pinfunction "28_28") (pintype "bidirectional"))
      (node (ref "X-NORTH") (pin "107") (pinfunction "107_107") (pintype "bidirectional"))
    )
    (net (code "166") (name "OUT64_N") (class "Default")
      (node (ref "X-NORTH") (pin "111") (pinfunction "111_111") (pintype "bidirectional"))
    )
    (net (code "167") (name "OUT64_P") (class "Default")
      (node (ref "X-NORTH") (pin "113") (pinfunction "113_113") (pintype "bidirectional"))
    )
    (net (code "168") (name "OUTCLK_N") (class "Default")
      (node (ref "X-NORTH") (pin "15") (pinfunction "15_15") (pintype "bidirectional"))
      (node (ref "X-WEST") (pin "53") (pinfunction "53_53") (pintype "bidirectional"))
    )
    (net (code "169") (name "OUTCLK_P") (class "Default")
      (node (ref "X-NORTH") (pin "17") (pinfunction "17_17") (pintype "bidirectional"))
      (node (ref "X-WEST") (pin "55") (pinfunction "55_55") (pintype "bidirectional"))
    )
    (net (code "170") (name "OUTCTR_N") (class "Default")
      (node (ref "X-SOUTH") (pin "125") (pinfunction "125_125") (pintype "bidirectional"))
      (node (ref "X-WEST") (pin "22") (pinfunction "22_22") (pintype "bidirectional"))
    )
    (net (code "171") (name "OUTCTR_P") (class "Default")
      (node (ref "X-SOUTH") (pin "123") (pinfunction "123_123") (pintype "bidirectional"))
      (node (ref "X-WEST") (pin "24") (pinfunction "24_24") (pintype "bidirectional"))
    )
    (net (code "172") (name "S00_N") (class "Default")
      (node (ref "X-SOUTH") (pin "16") (pinfunction "16_16") (pintype "bidirectional"))
    )
    (net (code "173") (name "S00_P") (class "Default")
      (node (ref "X-SOUTH") (pin "14") (pinfunction "14_14") (pintype "bidirectional"))
    )
    (net (code "174") (name "S01_N") (class "Default")
      (node (ref "X-SOUTH") (pin "17") (pinfunction "17_17") (pintype "bidirectional"))
    )
    (net (code "175") (name "S01_P") (class "Default")
      (node (ref "X-SOUTH") (pin "15") (pinfunction "15_15") (pintype "bidirectional"))
    )
    (net (code "176") (name "S02_N") (class "Default")
      (node (ref "X-SOUTH") (pin "22") (pinfunction "22_22") (pintype "bidirectional"))
    )
    (net (code "177") (name "S02_P") (class "Default")
      (node (ref "X-SOUTH") (pin "20") (pinfunction "20_20") (pintype "bidirectional"))
    )
    (net (code "178") (name "S03_N") (class "Default")
      (node (ref "X-SOUTH") (pin "23") (pinfunction "23_23") (pintype "bidirectional"))
    )
    (net (code "179") (name "S03_P") (class "Default")
      (node (ref "X-SOUTH") (pin "21") (pinfunction "21_21") (pintype "bidirectional"))
    )
    (net (code "180") (name "S05_N") (class "Default")
      (node (ref "X-SOUTH") (pin "29") (pinfunction "29_29") (pintype "bidirectional"))
    )
    (net (code "181") (name "S05_P") (class "Default")
      (node (ref "X-SOUTH") (pin "27") (pinfunction "27_27") (pintype "bidirectional"))
    )
    (net (code "182") (name "S38_N") (class "Default")
      (node (ref "X-SOUTH") (pin "130") (pinfunction "130_130") (pintype "bidirectional"))
    )
    (net (code "183") (name "S38_P") (class "Default")
      (node (ref "X-SOUTH") (pin "128") (pinfunction "128_128") (pintype "bidirectional"))
    )
    (net (code "184") (name "S39_N") (class "Default")
      (node (ref "X-SOUTH") (pin "131") (pinfunction "131_131") (pintype "bidirectional"))
    )
    (net (code "185") (name "S39_P") (class "Default")
      (node (ref "X-SOUTH") (pin "129") (pinfunction "129_129") (pintype "bidirectional"))
    )
    (net (code "186") (name "SPI_EN") (class "Default")
      (node (ref "X-EAST") (pin "14") (pinfunction "14_14") (pintype "bidirectional"))
      (node (ref "X-NORTH") (pin "119") (pinfunction "119_119") (pintype "bidirectional"))
    )
    (net (code "187") (name "SYS_RES_N") (class "Default")
      (node (ref "X-EAST") (pin "22") (pinfunction "22_22") (pintype "bidirectional"))
      (node (ref "X-NORTH") (pin "125") (pinfunction "125_125") (pintype "bidirectional"))
    )
    (net (code "188") (name "S_CHK_V") (class "Default")
      (node (ref "X-EAST") (pin "92") (pinfunction "92_92") (pintype "bidirectional"))
      (node (ref "X-EAST") (pin "94") (pinfunction "94_94") (pintype "bidirectional"))
      (node (ref "X-SOUTH") (pin "10") (pinfunction "10_10") (pintype "bidirectional"))
      (node (ref "X-SOUTH") (pin "8") (pinfunction "8_8") (pintype "bidirectional"))
    )
    (net (code "189") (name "S_I2C_V") (class "Default")
      (node (ref "X-SOUTH") (pin "135") (pinfunction "135_135") (pintype "bidirectional"))
      (node (ref "X-SOUTH") (pin "137") (pinfunction "137_137") (pintype "bidirectional"))
      (node (ref "X-WEST") (pin "7") (pinfunction "7_7") (pintype "bidirectional"))
      (node (ref "X-WEST") (pin "9") (pinfunction "9_9") (pintype "bidirectional"))
    )
    (net (code "190") (name "S_SCK") (class "Default")
      (node (ref "X-SOUTH") (pin "144") (pinfunction "144_144") (pintype "bidirectional"))
      (node (ref "X-WEST") (pin "2") (pinfunction "2_2") (pintype "bidirectional"))
    )
    (net (code "191") (name "S_SCL") (class "Default")
      (node (ref "X-SOUTH") (pin "143") (pinfunction "143_143") (pintype "bidirectional"))
      (node (ref "X-WEST") (pin "1") (pinfunction "1_1") (pintype "bidirectional"))
    )
    (net (code "192") (name "S_SDA") (class "Default")
      (node (ref "X-SOUTH") (pin "141") (pinfunction "141_141") (pintype "bidirectional"))
      (node (ref "X-WEST") (pin "3") (pinfunction "3_3") (pintype "bidirectional"))
    )
    (net (code "193") (name "S_SDI") (class "Default")
      (node (ref "X-SOUTH") (pin "140") (pinfunction "140_140") (pintype "bidirectional"))
      (node (ref "X-WEST") (pin "6") (pinfunction "6_6") (pintype "bidirectional"))
    )
    (net (code "194") (name "S_SDO") (class "Default")
      (node (ref "X-SOUTH") (pin "142") (pinfunction "142_142") (pintype "bidirectional"))
      (node (ref "X-WEST") (pin "4") (pinfunction "4_4") (pintype "bidirectional"))
    )
    (net (code "195") (name "S_SPI_V") (class "Default")
      (node (ref "X-SOUTH") (pin "134") (pinfunction "134_134") (pintype "bidirectional"))
      (node (ref "X-SOUTH") (pin "136") (pinfunction "136_136") (pintype "bidirectional"))
      (node (ref "X-WEST") (pin "10") (pinfunction "10_10") (pintype "bidirectional"))
      (node (ref "X-WEST") (pin "8") (pinfunction "8_8") (pintype "bidirectional"))
    )
    (net (code "196") (name "S_VE") (class "Default")
      (node (ref "C7") (pin "1") (pinfunction "1_1") (pintype "passive"))
      (node (ref "SE") (pin "1") (pinfunction "1_1") (pintype "passive"))
      (node (ref "X-SOUTH") (pin "13") (pinfunction "13_13") (pintype "bidirectional"))
      (node (ref "X-SOUTH") (pin "19") (pinfunction "19_19") (pintype "bidirectional"))
      (node (ref "X-SOUTH") (pin "25") (pinfunction "25_25") (pintype "bidirectional"))
      (node (ref "X-SOUTH") (pin "31") (pinfunction "31_31") (pintype "bidirectional"))
      (node (ref "X-SOUTH") (pin "37") (pinfunction "37_37") (pintype "bidirectional"))
    )
    (net (code "197") (name "S_VE_CV") (class "Default")
      (node (ref "X-EAST") (pin "100") (pinfunction "100_100") (pintype "bidirectional"))
      (node (ref "X-SOUTH") (pin "2") (pinfunction "2_2") (pintype "bidirectional"))
    )
    (net (code "198") (name "S_VE_OV") (class "Default")
      (node (ref "X-EAST") (pin "99") (pinfunction "99_99") (pintype "bidirectional"))
      (node (ref "X-SOUTH") (pin "1") (pinfunction "1_1") (pintype "bidirectional"))
    )
    (net (code "199") (name "S_VE_UV") (class "Default")
      (node (ref "X-EAST") (pin "89") (pinfunction "89_89") (pintype "bidirectional"))
      (node (ref "X-SOUTH") (pin "7") (pinfunction "7_7") (pintype "bidirectional"))
    )
    (net (code "200") (name "S_VS") (class "Default")
      (node (ref "C6") (pin "1") (pinfunction "1_1") (pintype "passive"))
      (node (ref "SW") (pin "1") (pinfunction "1_1") (pintype "passive"))
      (node (ref "X-SOUTH") (pin "49") (pinfunction "49_49") (pintype "bidirectional"))
      (node (ref "X-SOUTH") (pin "55") (pinfunction "55_55") (pintype "bidirectional"))
      (node (ref "X-SOUTH") (pin "61") (pinfunction "61_61") (pintype "bidirectional"))
      (node (ref "X-SOUTH") (pin "67") (pinfunction "67_67") (pintype "bidirectional"))
      (node (ref "X-SOUTH") (pin "73") (pinfunction "73_73") (pintype "bidirectional"))
      (node (ref "X-SOUTH") (pin "79") (pinfunction "79_79") (pintype "bidirectional"))
      (node (ref "X-SOUTH") (pin "85") (pinfunction "85_85") (pintype "bidirectional"))
      (node (ref "X-SOUTH") (pin "91") (pinfunction "91_91") (pintype "bidirectional"))
      (node (ref "X-SOUTH") (pin "97") (pinfunction "97_97") (pintype "bidirectional"))
    )
    (net (code "201") (name "S_VS_CV") (class "Default")
      (node (ref "X-EAST") (pin "98") (pinfunction "98_98") (pintype "bidirectional"))
      (node (ref "X-SOUTH") (pin "4") (pinfunction "4_4") (pintype "bidirectional"))
    )
    (net (code "202") (name "S_VS_OV") (class "Default")
      (node (ref "X-EAST") (pin "97") (pinfunction "97_97") (pintype "bidirectional"))
      (node (ref "X-SOUTH") (pin "3") (pinfunction "3_3") (pintype "bidirectional"))
    )
    (net (code "203") (name "S_VS_UV") (class "Default")
      (node (ref "X-EAST") (pin "87") (pinfunction "87_87") (pintype "bidirectional"))
      (node (ref "X-SOUTH") (pin "9") (pinfunction "9_9") (pintype "bidirectional"))
    )
    (net (code "204") (name "S_VW") (class "Default")
      (node (ref "C2") (pin "1") (pinfunction "1_1") (pintype "passive"))
      (node (ref "SW") (pin "2") (pinfunction "2_2") (pintype "passive"))
      (node (ref "X-SOUTH") (pin "109") (pinfunction "109_109") (pintype "bidirectional"))
      (node (ref "X-SOUTH") (pin "115") (pinfunction "115_115") (pintype "bidirectional"))
      (node (ref "X-SOUTH") (pin "121") (pinfunction "121_121") (pintype "bidirectional"))
      (node (ref "X-SOUTH") (pin "127") (pinfunction "127_127") (pintype "bidirectional"))
      (node (ref "X-SOUTH") (pin "133") (pinfunction "133_133") (pintype "bidirectional"))
    )
    (net (code "205") (name "S_VW_CV") (class "Default")
      (node (ref "X-EAST") (pin "96") (pinfunction "96_96") (pintype "bidirectional"))
      (node (ref "X-SOUTH") (pin "6") (pinfunction "6_6") (pintype "bidirectional"))
    )
    (net (code "206") (name "S_VW_OV") (class "Default")
      (node (ref "X-EAST") (pin "95") (pinfunction "95_95") (pintype "bidirectional"))
      (node (ref "X-SOUTH") (pin "5") (pinfunction "5_5") (pintype "bidirectional"))
    )
    (net (code "207") (name "S_VW_UV") (class "Default")
      (node (ref "X-EAST") (pin "85") (pinfunction "85_85") (pintype "bidirectional"))
      (node (ref "X-SOUTH") (pin "11") (pinfunction "11_11") (pintype "bidirectional"))
    )
    (net (code "208") (name "TCK") (class "Default")
      (node (ref "X-WEST") (pin "12") (pinfunction "12_12") (pintype "bidirectional"))
    )
    (net (code "209") (name "TDI") (class "Default")
      (node (ref "X-WEST") (pin "16") (pinfunction "16_16") (pintype "bidirectional"))
    )
    (net (code "210") (name "TDIG1") (class "Default")
      (node (ref "X-EAST") (pin "18") (pinfunction "18_18") (pintype "bidirectional"))
      (node (ref "X-NORTH") (pin "123") (pinfunction "123_123") (pintype "bidirectional"))
    )
    (net (code "211") (name "TDIG2") (class "Default")
      (node (ref "X-EAST") (pin "17") (pinfunction "17_17") (pintype "bidirectional"))
      (node (ref "X-NORTH") (pin "130") (pinfunction "130_130") (pintype "bidirectional"))
    )
    (net (code "212") (name "TDO") (class "Default")
      (node (ref "X-WEST") (pin "18") (pinfunction "18_18") (pintype "bidirectional"))
    )
    (net (code "213") (name "TMS") (class "Default")
      (node (ref "X-WEST") (pin "14") (pinfunction "14_14") (pintype "bidirectional"))
    )
    (net (code "214") (name "T_EXP1") (class "Default")
      (node (ref "X-EAST") (pin "12") (pinfunction "12_12") (pintype "bidirectional"))
      (node (ref "X-NORTH") (pin "131") (pinfunction "131_131") (pintype "bidirectional"))
    )
    (net (code "215") (name "T_EXP2") (class "Default")
      (node (ref "X-EAST") (pin "16") (pinfunction "16_16") (pintype "bidirectional"))
      (node (ref "X-NORTH") (pin "117") (pinfunction "117_117") (pintype "bidirectional"))
    )
    (net (code "216") (name "W_I2C_V") (class "Default")
      (node (ref "X-WEST") (pin "11") (pinfunction "11_11") (pintype "bidirectional"))
      (node (ref "X-WEST") (pin "13") (pinfunction "13_13") (pintype "bidirectional"))
    )
    (net (code "217") (name "W_SCL") (class "Default")
      (node (ref "X-WEST") (pin "15") (pinfunction "15_15") (pintype "bidirectional"))
    )
    (net (code "218") (name "W_SDA") (class "Default")
      (node (ref "X-WEST") (pin "17") (pinfunction "17_17") (pintype "bidirectional"))
    )
    (net (code "219") (name "W_VW") (class "Default")
      (node (ref "C8") (pin "1") (pinfunction "1_1") (pintype "passive"))
      (node (ref "NW") (pin "2") (pinfunction "2_2") (pintype "passive"))
      (node (ref "X-WEST") (pin "79") (pinfunction "79_79") (pintype "bidirectional"))
      (node (ref "X-WEST") (pin "81") (pinfunction "81_81") (pintype "bidirectional"))
      (node (ref "X-WEST") (pin "83") (pinfunction "83_83") (pintype "bidirectional"))
      (node (ref "X-WEST") (pin "84") (pinfunction "84_84") (pintype "bidirectional"))
      (node (ref "X-WEST") (pin "86") (pinfunction "86_86") (pintype "bidirectional"))
      (node (ref "X-WEST") (pin "88") (pinfunction "88_88") (pintype "bidirectional"))
    )
    (net (code "220") (name "W_VW_CV") (class "Default")
      (node (ref "X-WEST") (pin "90") (pinfunction "90_90") (pintype "bidirectional"))
    )
    (net (code "221") (name "W_VW_OV") (class "Default")
      (node (ref "X-WEST") (pin "93") (pinfunction "93_93") (pintype "bidirectional"))
    )
    (net (code "222") (name "W_VW_UV") (class "Default")
      (node (ref "X-WEST") (pin "91") (pinfunction "91_91") (pintype "bidirectional"))
    )
    (net (code "223") (name "unconnected-(X-EAST-PadM1)") (class "Default")
      (node (ref "X-EAST") (pin "M1") (pinfunction "M1_M1") (pintype "bidirectional"))
    )
    (net (code "224") (name "unconnected-(X-EAST-PadM2)") (class "Default")
      (node (ref "X-EAST") (pin "M2") (pinfunction "M2_M2") (pintype "bidirectional"))
    )
    (net (code "225") (name "unconnected-(X-NORTH-PadM1)") (class "Default")
      (node (ref "X-NORTH") (pin "M1") (pinfunction "M1_M1") (pintype "bidirectional"))
    )
    (net (code "226") (name "unconnected-(X-NORTH-PadM2)") (class "Default")
      (node (ref "X-NORTH") (pin "M2") (pinfunction "M2_M2") (pintype "bidirectional"))
    )
    (net (code "227") (name "unconnected-(X-SOUTH-PadM1)") (class "Default")
      (node (ref "X-SOUTH") (pin "M1") (pinfunction "M1_M1") (pintype "bidirectional"))
    )
    (net (code "228") (name "unconnected-(X-SOUTH-PadM2)") (class "Default")
      (node (ref "X-SOUTH") (pin "M2") (pinfunction "M2_M2") (pintype "bidirectional"))
    )
    (net (code "229") (name "unconnected-(X-WEST-PadM1)") (class "Default")
      (node (ref "X-WEST") (pin "M1") (pinfunction "M1_M1") (pintype "bidirectional"))
    )
    (net (code "230") (name "unconnected-(X-WEST-PadM2)") (class "Default")
      (node (ref "X-WEST") (pin "M2") (pinfunction "M2_M2") (pintype "bidirectional"))
    )
  )
)
